# POWER.net
KiCad netlist of a schematic drawn in Altium Designer
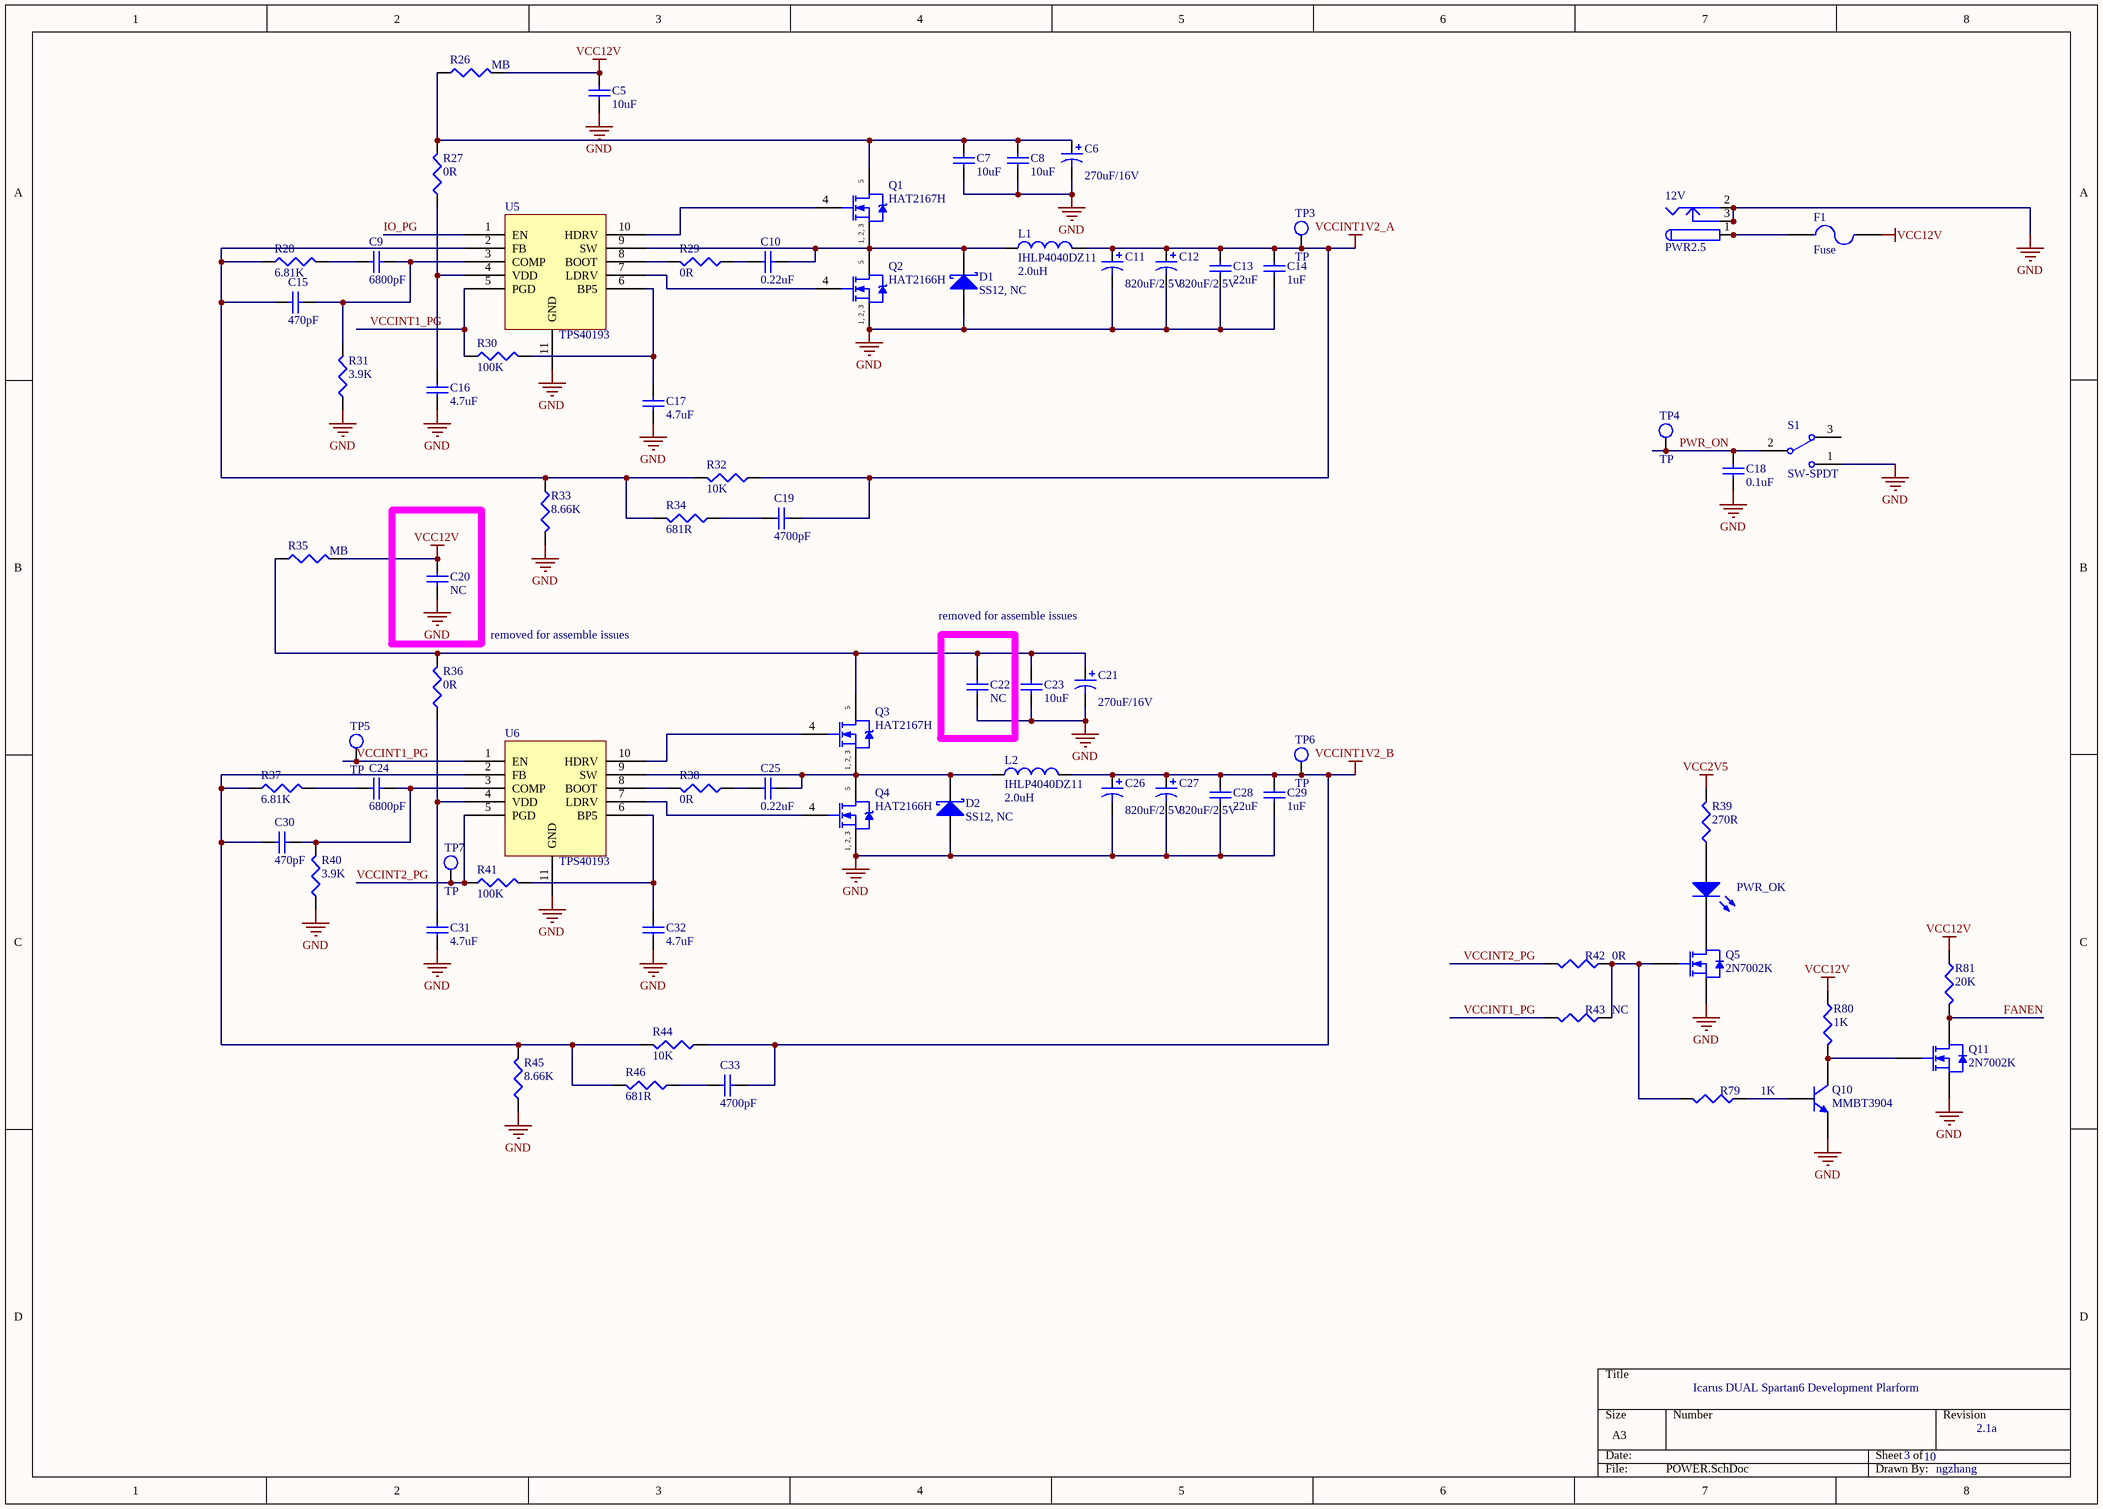
[diagram p0: POWER.SchDoc]

(export (version "E")
  (design (tool "Eeschema 10.0.6"))
  (components
    (comp (ref "12V")
      (value "PWR2.5")
      (footprint "KLD-0202")
      (description "Low Voltage Power Supply Connector")
      (fields (field (name "PUBLISHER") "Altium Limited"))
      (libsource (lib "Miscellaneous Connectors") (part "PWR2.5"))
    )
    (comp (ref "C5")
      (value "10uF")
      (footprint "C1206")
      (description "Capacitor (Semiconductor SIM Model)")
      (fields (field (name "PUBLISHER") "Altium Limited"))
      (libsource (lib "Miscellaneous Devices") (part "Cap Semi"))
    )
    (comp (ref "C6")
      (value "270uF/16V")
      (footprint "CAP8X8")
      (description "Polarized Capacitor (Radial)")
      (fields (field (name "PUBLISHER") "Altium Limited"))
      (libsource (lib "Miscellaneous Devices") (part "Cap Pol1"))
    )
    (comp (ref "C7")
      (value "10uF")
      (footprint "C1206")
      (description "Capacitor (Semiconductor SIM Model)")
      (fields (field (name "PUBLISHER") "Altium Limited"))
      (libsource (lib "Miscellaneous Devices") (part "Cap Semi"))
    )
    (comp (ref "C8")
      (value "10uF")
      (footprint "C1206")
      (description "Capacitor (Semiconductor SIM Model)")
      (fields (field (name "PUBLISHER") "Altium Limited"))
      (libsource (lib "Miscellaneous Devices") (part "Cap Semi"))
    )
    (comp (ref "C9")
      (value "6800pF")
      (footprint "1608[0603]")
      (description "Capacitor (Semiconductor SIM Model)")
      (fields (field (name "PUBLISHER") "Altium Limited"))
      (libsource (lib "Miscellaneous Devices") (part "Cap Semi"))
    )
    (comp (ref "C10")
      (value "0.22uF")
      (footprint "1608[0603]")
      (description "Capacitor (Semiconductor SIM Model)")
      (fields (field (name "PUBLISHER") "Altium Limited"))
      (libsource (lib "Miscellaneous Devices") (part "Cap Semi"))
    )
    (comp (ref "C11")
      (value "820uF/2.5V")
      (footprint "CAP8X8")
      (description "Polarized Capacitor (Radial)")
      (fields (field (name "PUBLISHER") "Altium Limited"))
      (libsource (lib "Miscellaneous Devices") (part "Cap Pol1"))
    )
    (comp (ref "C12")
      (value "820uF/2.5V")
      (footprint "CAP8X8")
      (description "Polarized Capacitor (Radial)")
      (fields (field (name "PUBLISHER") "Altium Limited"))
      (libsource (lib "Miscellaneous Devices") (part "Cap Pol1"))
    )
    (comp (ref "C13")
      (value "22uF")
      (footprint "C1206")
      (description "Capacitor (Semiconductor SIM Model)")
      (fields (field (name "PUBLISHER") "Altium Limited"))
      (libsource (lib "Miscellaneous Devices") (part "Cap Semi"))
    )
    (comp (ref "C14")
      (value "1uF")
      (footprint "1608[0603]")
      (description "Capacitor (Semiconductor SIM Model)")
      (fields (field (name "PUBLISHER") "Altium Limited"))
      (libsource (lib "Miscellaneous Devices") (part "Cap Semi"))
    )
    (comp (ref "C15")
      (value "470pF")
      (footprint "1608[0603]")
      (description "Capacitor (Semiconductor SIM Model)")
      (fields (field (name "PUBLISHER") "Altium Limited"))
      (libsource (lib "Miscellaneous Devices") (part "Cap Semi"))
    )
    (comp (ref "C16")
      (value "4.7uF")
      (footprint "C0805")
      (description "Capacitor (Semiconductor SIM Model)")
      (fields (field (name "PUBLISHER") "Altium Limited"))
      (libsource (lib "Miscellaneous Devices") (part "Cap Semi"))
    )
    (comp (ref "C17")
      (value "4.7uF")
      (footprint "C0805")
      (description "Capacitor (Semiconductor SIM Model)")
      (fields (field (name "PUBLISHER") "Altium Limited"))
      (libsource (lib "Miscellaneous Devices") (part "Cap Semi"))
    )
    (comp (ref "C18")
      (value "0.1uF")
      (footprint "1608[0603]")
      (description "Capacitor (Semiconductor SIM Model)")
      (fields (field (name "PUBLISHER") "Altium Limited"))
      (libsource (lib "Miscellaneous Devices") (part "Cap Semi"))
    )
    (comp (ref "C19")
      (value "4700pF")
      (footprint "1608[0603]")
      (description "Capacitor (Semiconductor SIM Model)")
      (fields (field (name "PUBLISHER") "Altium Limited"))
      (libsource (lib "Miscellaneous Devices") (part "Cap Semi"))
    )
    (comp (ref "C20")
      (value "NC")
      (footprint "C1206")
      (description "Capacitor (Semiconductor SIM Model)")
      (fields (field (name "PUBLISHER") "Altium Limited"))
      (libsource (lib "Miscellaneous Devices") (part "Cap Semi"))
    )
    (comp (ref "C21")
      (value "270uF/16V")
      (footprint "CAP8X8")
      (description "Polarized Capacitor (Radial)")
      (fields (field (name "PUBLISHER") "Altium Limited"))
      (libsource (lib "Miscellaneous Devices") (part "Cap Pol1"))
    )
    (comp (ref "C22")
      (value "NC")
      (footprint "C1206")
      (description "Capacitor (Semiconductor SIM Model)")
      (fields (field (name "PUBLISHER") "Altium Limited"))
      (libsource (lib "Miscellaneous Devices") (part "Cap Semi"))
    )
    (comp (ref "C23")
      (value "10uF")
      (footprint "C1206")
      (description "Capacitor (Semiconductor SIM Model)")
      (fields (field (name "PUBLISHER") "Altium Limited"))
      (libsource (lib "Miscellaneous Devices") (part "Cap Semi"))
    )
    (comp (ref "C24")
      (value "6800pF")
      (footprint "1608[0603]")
      (description "Capacitor (Semiconductor SIM Model)")
      (fields (field (name "PUBLISHER") "Altium Limited"))
      (libsource (lib "Miscellaneous Devices") (part "Cap Semi"))
    )
    (comp (ref "C25")
      (value "0.22uF")
      (footprint "1608[0603]")
      (description "Capacitor (Semiconductor SIM Model)")
      (fields (field (name "PUBLISHER") "Altium Limited"))
      (libsource (lib "Miscellaneous Devices") (part "Cap Semi"))
    )
    (comp (ref "C26")
      (value "820uF/2.5V")
      (footprint "CAP8X8")
      (description "Polarized Capacitor (Radial)")
      (fields (field (name "PUBLISHER") "Altium Limited"))
      (libsource (lib "Miscellaneous Devices") (part "Cap Pol1"))
    )
    (comp (ref "C27")
      (value "820uF/2.5V")
      (footprint "CAP8X8")
      (description "Polarized Capacitor (Radial)")
      (fields (field (name "PUBLISHER") "Altium Limited"))
      (libsource (lib "Miscellaneous Devices") (part "Cap Pol1"))
    )
    (comp (ref "C28")
      (value "22uF")
      (footprint "C1206")
      (description "Capacitor (Semiconductor SIM Model)")
      (fields (field (name "PUBLISHER") "Altium Limited"))
      (libsource (lib "Miscellaneous Devices") (part "Cap Semi"))
    )
    (comp (ref "C29")
      (value "1uF")
      (footprint "1608[0603]")
      (description "Capacitor (Semiconductor SIM Model)")
      (fields (field (name "PUBLISHER") "Altium Limited"))
      (libsource (lib "Miscellaneous Devices") (part "Cap Semi"))
    )
    (comp (ref "C30")
      (value "470pF")
      (footprint "1608[0603]")
      (description "Capacitor (Semiconductor SIM Model)")
      (fields (field (name "PUBLISHER") "Altium Limited"))
      (libsource (lib "Miscellaneous Devices") (part "Cap Semi"))
    )
    (comp (ref "C31")
      (value "4.7uF")
      (footprint "C0805")
      (description "Capacitor (Semiconductor SIM Model)")
      (fields (field (name "PUBLISHER") "Altium Limited"))
      (libsource (lib "Miscellaneous Devices") (part "Cap Semi"))
    )
    (comp (ref "C32")
      (value "4.7uF")
      (footprint "C0805")
      (description "Capacitor (Semiconductor SIM Model)")
      (fields (field (name "PUBLISHER") "Altium Limited"))
      (libsource (lib "Miscellaneous Devices") (part "Cap Semi"))
    )
    (comp (ref "C33")
      (value "4700pF")
      (footprint "1608[0603]")
      (description "Capacitor (Semiconductor SIM Model)")
      (fields (field (name "PUBLISHER") "Altium Limited"))
      (libsource (lib "Miscellaneous Devices") (part "Cap Semi"))
    )
    (comp (ref "D1")
      (value "SS12, NC")
      (footprint "SMA")
      (description "Schottky Rectifier")
      (fields (field (name "PUBLISHER") "Altium Limited"))
      (libsource (lib "IR Rectifier - Schottky") (part "10MQ060N"))
    )
    (comp (ref "D2")
      (value "SS12, NC")
      (footprint "SMA")
      (description "Schottky Rectifier")
      (fields (field (name "PUBLISHER") "Altium Limited"))
      (libsource (lib "IR Rectifier - Schottky") (part "10MQ060N"))
    )
    (comp (ref "F1")
      (value "Fuse")
      (footprint "12Z-2010")
      (fields (field (name "PUBLISHER") "Altium Limited"))
      (libsource (lib "Miscellaneous Devices") (part "Fuse 2"))
    )
    (comp (ref "L1")
      (value "IHLP4040DZ11")
      (footprint "IHLP4040")
      (description "Inductor")
      (fields (field (name "ALTIUM_VALUE") "2.0uH") (field (name "PUBLISHER") "Altium Limited"))
      (libsource (lib "Miscellaneous Devices") (part "Inductor"))
    )
    (comp (ref "L2")
      (value "IHLP4040DZ11")
      (footprint "IHLP4040")
      (description "Inductor")
      (fields (field (name "ALTIUM_VALUE") "2.0uH") (field (name "PUBLISHER") "Altium Limited"))
      (libsource (lib "Miscellaneous Devices") (part "Inductor"))
    )
    (comp (ref "PWR_OK")
      (value "LED3")
      (footprint "CD1608-0603")
      (description "Typical BLUE SiC LED")
      (fields (field (name "PUBLISHER") "Altium Limited"))
      (libsource (lib "Miscellaneous Devices") (part "LED3"))
    )
    (comp (ref "Q1") (value "HAT2167H") (footprint "LFPAK") (libsource (lib "S6") (part "HAT216X")))
    (comp (ref "Q2") (value "HAT2166H") (footprint "LFPAK") (libsource (lib "S6") (part "HAT216X")))
    (comp (ref "Q3") (value "HAT2167H") (footprint "LFPAK") (libsource (lib "S6") (part "HAT216X")))
    (comp (ref "Q4") (value "HAT2166H") (footprint "LFPAK") (libsource (lib "S6") (part "HAT216X")))
    (comp (ref "Q5")
      (value "2N7002K")
      (footprint "SOT23_N")
      (description "N-channel Enhancement Mode Field-effect Transistor")
      (fields (field (name "PUBLISHER") "Altium Limited"))
      (libsource (lib "Philips Discrete MOSFET - Low Power") (part "2N7002"))
    )
    (comp (ref "Q10")
      (value "MMBT3904")
      (footprint "SOT23_N")
      (description "NPN Switching Transistor")
      (fields (field (name "PUBLISHER") "Altium Limited"))
      (libsource (lib "Philips Discrete BJT - Low Power") (part "MMBT3904"))
    )
    (comp (ref "Q11")
      (value "2N7002K")
      (footprint "SOT23_N")
      (description "N-channel Enhancement Mode Field-effect Transistor")
      (fields (field (name "PUBLISHER") "Altium Limited"))
      (libsource (lib "Philips Discrete MOSFET - Low Power") (part "2N7002"))
    )
    (comp (ref "R26")
      (value "MB")
      (footprint "C1206")
      (description "Resistor")
      (fields (field (name "PUBLISHER") "Altium Limited"))
      (libsource (lib "Miscellaneous Devices") (part "Res3"))
    )
    (comp (ref "R27")
      (value "0R")
      (footprint "J1-0603")
      (description "Resistor")
      (fields (field (name "PUBLISHER") "Altium Limited"))
      (libsource (lib "Miscellaneous Devices") (part "Res3"))
    )
    (comp (ref "R28")
      (value "6.81K")
      (footprint "J1-0603")
      (description "Resistor")
      (fields (field (name "PUBLISHER") "Altium Limited"))
      (libsource (lib "Miscellaneous Devices") (part "Res3"))
    )
    (comp (ref "R29")
      (value "0R")
      (footprint "J1-0603")
      (description "Resistor")
      (fields (field (name "PUBLISHER") "Altium Limited"))
      (libsource (lib "Miscellaneous Devices") (part "Res3"))
    )
    (comp (ref "R30")
      (value "100K")
      (footprint "J1-0603")
      (description "Resistor")
      (fields (field (name "PUBLISHER") "Altium Limited"))
      (libsource (lib "Miscellaneous Devices") (part "Res3"))
    )
    (comp (ref "R31")
      (value "3.9K")
      (footprint "J1-0603")
      (description "Resistor")
      (fields (field (name "PUBLISHER") "Altium Limited"))
      (libsource (lib "Miscellaneous Devices") (part "Res3"))
    )
    (comp (ref "R32")
      (value "10K")
      (footprint "J1-0603")
      (description "Resistor")
      (fields (field (name "PUBLISHER") "Altium Limited"))
      (libsource (lib "Miscellaneous Devices") (part "Res3"))
    )
    (comp (ref "R33")
      (value "8.66K")
      (footprint "J1-0603")
      (description "Resistor")
      (fields (field (name "PUBLISHER") "Altium Limited"))
      (libsource (lib "Miscellaneous Devices") (part "Res3"))
    )
    (comp (ref "R34")
      (value "681R")
      (footprint "J1-0603")
      (description "Resistor")
      (fields (field (name "PUBLISHER") "Altium Limited"))
      (libsource (lib "Miscellaneous Devices") (part "Res3"))
    )
    (comp (ref "R35")
      (value "MB")
      (footprint "C1206")
      (description "Resistor")
      (fields (field (name "PUBLISHER") "Altium Limited"))
      (libsource (lib "Miscellaneous Devices") (part "Res3"))
    )
    (comp (ref "R36")
      (value "0R")
      (footprint "J1-0603")
      (description "Resistor")
      (fields (field (name "PUBLISHER") "Altium Limited"))
      (libsource (lib "Miscellaneous Devices") (part "Res3"))
    )
    (comp (ref "R37")
      (value "6.81K")
      (footprint "J1-0603")
      (description "Resistor")
      (fields (field (name "PUBLISHER") "Altium Limited"))
      (libsource (lib "Miscellaneous Devices") (part "Res3"))
    )
    (comp (ref "R38")
      (value "0R")
      (footprint "J1-0603")
      (description "Resistor")
      (fields (field (name "PUBLISHER") "Altium Limited"))
      (libsource (lib "Miscellaneous Devices") (part "Res3"))
    )
    (comp (ref "R39")
      (value "270R")
      (footprint "J1-0603")
      (description "Resistor")
      (fields (field (name "PUBLISHER") "Altium Limited"))
      (libsource (lib "Miscellaneous Devices") (part "Res3"))
    )
    (comp (ref "R40")
      (value "3.9K")
      (footprint "J1-0603")
      (description "Resistor")
      (fields (field (name "PUBLISHER") "Altium Limited"))
      (libsource (lib "Miscellaneous Devices") (part "Res3"))
    )
    (comp (ref "R41")
      (value "100K")
      (footprint "J1-0603")
      (description "Resistor")
      (fields (field (name "PUBLISHER") "Altium Limited"))
      (libsource (lib "Miscellaneous Devices") (part "Res3"))
    )
    (comp (ref "R42")
      (value "0R")
      (footprint "J1-0603")
      (description "Resistor")
      (fields (field (name "PUBLISHER") "Altium Limited"))
      (libsource (lib "Miscellaneous Devices") (part "Res3"))
    )
    (comp (ref "R43")
      (value "NC")
      (footprint "J1-0603")
      (description "Resistor")
      (fields (field (name "PUBLISHER") "Altium Limited"))
      (libsource (lib "Miscellaneous Devices") (part "Res3"))
    )
    (comp (ref "R44")
      (value "10K")
      (footprint "J1-0603")
      (description "Resistor")
      (fields (field (name "PUBLISHER") "Altium Limited"))
      (libsource (lib "Miscellaneous Devices") (part "Res3"))
    )
    (comp (ref "R45")
      (value "8.66K")
      (footprint "J1-0603")
      (description "Resistor")
      (fields (field (name "PUBLISHER") "Altium Limited"))
      (libsource (lib "Miscellaneous Devices") (part "Res3"))
    )
    (comp (ref "R46")
      (value "681R")
      (footprint "J1-0603")
      (description "Resistor")
      (fields (field (name "PUBLISHER") "Altium Limited"))
      (libsource (lib "Miscellaneous Devices") (part "Res3"))
    )
    (comp (ref "R79")
      (value "1K")
      (footprint "J1-0603")
      (description "Resistor")
      (fields (field (name "PUBLISHER") "Altium Limited"))
      (libsource (lib "Miscellaneous Devices") (part "Res3"))
    )
    (comp (ref "R80")
      (value "1K")
      (footprint "J1-0603")
      (description "Resistor")
      (fields (field (name "PUBLISHER") "Altium Limited"))
      (libsource (lib "Miscellaneous Devices") (part "Res3"))
    )
    (comp (ref "R81")
      (value "20K")
      (footprint "J1-0603")
      (description "Resistor")
      (fields (field (name "PUBLISHER") "Altium Limited"))
      (libsource (lib "Miscellaneous Devices") (part "Res3"))
    )
    (comp (ref "S1")
      (value "SW-SPDT")
      (footprint "SW_3")
      (description "SPDT Subminiature Toggle Switch, Right Angle Mounting, Vertical Actuation")
      (fields (field (name "PUBLISHER") "Altium Limited"))
      (libsource (lib "Miscellaneous Devices") (part "SW-SPDT"))
    )
    (comp (ref "TP3") (value "TP") (footprint "TP") (libsource (lib "S6") (part "TP")))
    (comp (ref "TP4") (value "TP") (footprint "TP") (libsource (lib "S6") (part "TP")))
    (comp (ref "TP5") (value "TP") (footprint "TP") (libsource (lib "S6") (part "TP")))
    (comp (ref "TP6") (value "TP") (footprint "TP") (libsource (lib "S6") (part "TP")))
    (comp (ref "TP7") (value "TP") (footprint "TP") (libsource (lib "S6") (part "TP")))
    (comp (ref "U5") (value "TPS40193") (footprint "SON10") (libsource (lib "S6") (part "TPS40193")))
    (comp (ref "U6") (value "TPS40193") (footprint "SON10") (libsource (lib "S6") (part "TPS40193")))
  )
  (nets
    (net (code "1") (name "/FANEN") (class "Default")
      (node (ref "Q11") (pin "3") (pinfunction "D_3") (pintype "passive"))
      (node (ref "R81") (pin "2") (pinfunction "2_2") (pintype "passive"))
    )
    (net (code "2") (name "/IO_PG") (class "Default")
      (node (ref "U5") (pin "1") (pinfunction "EN_1") (pintype "passive"))
    )
    (net (code "3") (name "/PWR_ON") (class "Default")
      (node (ref "C18") (pin "2") (pinfunction "2_2") (pintype "passive"))
      (node (ref "S1") (pin "2") (pinfunction "2_2") (pintype "passive"))
      (node (ref "TP4") (pin "1") (pinfunction "TP_1") (pintype "passive"))
    )
    (net (code "4") (name "/VCCINT1_PG") (class "Default")
      (node (ref "R30") (pin "1") (pinfunction "1_1") (pintype "passive"))
      (node (ref "R43") (pin "2") (pinfunction "2_2") (pintype "passive"))
      (node (ref "TP5") (pin "1") (pinfunction "TP_1") (pintype "passive"))
      (node (ref "U5") (pin "5") (pinfunction "PGD_5") (pintype "passive"))
      (node (ref "U6") (pin "1") (pinfunction "EN_1") (pintype "passive"))
    )
    (net (code "5") (name "/VCCINT2_PG") (class "Default")
      (node (ref "R41") (pin "1") (pinfunction "1_1") (pintype "passive"))
      (node (ref "R42") (pin "2") (pinfunction "2_2") (pintype "passive"))
      (node (ref "TP7") (pin "1") (pinfunction "TP_1") (pintype "passive"))
      (node (ref "U6") (pin "5") (pinfunction "PGD_5") (pintype "passive"))
    )
    (net (code "6") (name "GND") (class "Default")
      (node (ref "12V") (pin "2") (pinfunction "2_2") (pintype "power_in"))
      (node (ref "12V") (pin "2A") (pinfunction "2A_2A") (pintype "power_in"))
      (node (ref "12V") (pin "2B") (pinfunction "2B_2B") (pintype "power_in"))
      (node (ref "12V") (pin "3") (pinfunction "3_3") (pintype "power_in"))
      (node (ref "12V") (pin "3A") (pinfunction "3A_3A") (pintype "power_in"))
      (node (ref "12V") (pin "3B") (pinfunction "3B_3B") (pintype "power_in"))
      (node (ref "C11") (pin "2") (pinfunction "2_2") (pintype "passive"))
      (node (ref "C12") (pin "2") (pinfunction "2_2") (pintype "passive"))
      (node (ref "C13") (pin "1") (pinfunction "1_1") (pintype "passive"))
      (node (ref "C14") (pin "1") (pinfunction "1_1") (pintype "passive"))
      (node (ref "C16") (pin "2") (pinfunction "2_2") (pintype "passive"))
      (node (ref "C17") (pin "1") (pinfunction "1_1") (pintype "passive"))
      (node (ref "C18") (pin "1") (pinfunction "1_1") (pintype "passive"))
      (node (ref "C20") (pin "1") (pinfunction "1_1") (pintype "passive"))
      (node (ref "C21") (pin "2") (pinfunction "2_2") (pintype "passive"))
      (node (ref "C22") (pin "1") (pinfunction "1_1") (pintype "passive"))
      (node (ref "C23") (pin "1") (pinfunction "1_1") (pintype "passive"))
      (node (ref "C26") (pin "2") (pinfunction "2_2") (pintype "passive"))
      (node (ref "C27") (pin "2") (pinfunction "2_2") (pintype "passive"))
      (node (ref "C28") (pin "1") (pinfunction "1_1") (pintype "passive"))
      (node (ref "C29") (pin "1") (pinfunction "1_1") (pintype "passive"))
      (node (ref "C31") (pin "1") (pinfunction "1_1") (pintype "passive"))
      (node (ref "C32") (pin "2") (pinfunction "2_2") (pintype "passive"))
      (node (ref "C5") (pin "1") (pinfunction "1_1") (pintype "passive"))
      (node (ref "C6") (pin "2") (pinfunction "2_2") (pintype "passive"))
      (node (ref "C7") (pin "1") (pinfunction "1_1") (pintype "passive"))
      (node (ref "C8") (pin "1") (pinfunction "1_1") (pintype "passive"))
      (node (ref "D1") (pin "1") (pinfunction "A_1") (pintype "passive"))
      (node (ref "D2") (pin "1") (pinfunction "A_1") (pintype "passive"))
      (node (ref "Q10") (pin "2") (pinfunction "E_2") (pintype "passive"))
      (node (ref "Q11") (pin "2") (pinfunction "S_2") (pintype "passive"))
      (node (ref "Q2") (pin "1") (pinfunction "S_1") (pintype "passive"))
      (node (ref "Q2") (pin "2") (pinfunction "S_2") (pintype "passive"))
      (node (ref "Q2") (pin "3") (pinfunction "S_3") (pintype "passive"))
      (node (ref "Q4") (pin "1") (pinfunction "S_1") (pintype "passive"))
      (node (ref "Q4") (pin "2") (pinfunction "S_2") (pintype "passive"))
      (node (ref "Q4") (pin "3") (pinfunction "S_3") (pintype "passive"))
      (node (ref "Q5") (pin "2") (pinfunction "S_2") (pintype "passive"))
      (node (ref "R31") (pin "1") (pinfunction "1_1") (pintype "passive"))
      (node (ref "R33") (pin "2") (pinfunction "2_2") (pintype "passive"))
      (node (ref "R40") (pin "1") (pinfunction "1_1") (pintype "passive"))
      (node (ref "R45") (pin "1") (pinfunction "1_1") (pintype "passive"))
      (node (ref "S1") (pin "1") (pinfunction "1_1") (pintype "passive"))
      (node (ref "U5") (pin "11") (pinfunction "GND_11") (pintype "passive"))
      (node (ref "U6") (pin "11") (pinfunction "GND_11") (pintype "passive"))
    )
    (net (code "7") (name "Net-(12V-Pad1)") (class "Default")
      (node (ref "12V") (pin "1") (pinfunction "1_1") (pintype "power_in"))
      (node (ref "12V") (pin "1A") (pinfunction "1A_1A") (pintype "power_in"))
      (node (ref "12V") (pin "1B") (pinfunction "1B_1B") (pintype "power_in"))
      (node (ref "F1") (pin "1") (pinfunction "1_1") (pintype "passive"))
    )
    (net (code "8") (name "Net-(C9-Pad2)") (class "Default")
      (node (ref "C9") (pin "2") (pinfunction "2_2") (pintype "passive"))
      (node (ref "R28") (pin "2") (pinfunction "2_2") (pintype "passive"))
    )
    (net (code "9") (name "Net-(C10-Pad2)") (class "Default")
      (node (ref "C10") (pin "2") (pinfunction "2_2") (pintype "passive"))
      (node (ref "R29") (pin "1") (pinfunction "1_1") (pintype "passive"))
    )
    (net (code "10") (name "Net-(C19-Pad1)") (class "Default")
      (node (ref "C19") (pin "1") (pinfunction "1_1") (pintype "passive"))
      (node (ref "R34") (pin "1") (pinfunction "1_1") (pintype "passive"))
    )
    (net (code "11") (name "Net-(C24-Pad2)") (class "Default")
      (node (ref "C24") (pin "2") (pinfunction "2_2") (pintype "passive"))
      (node (ref "R37") (pin "2") (pinfunction "2_2") (pintype "passive"))
    )
    (net (code "12") (name "Net-(C25-Pad2)") (class "Default")
      (node (ref "C25") (pin "2") (pinfunction "2_2") (pintype "passive"))
      (node (ref "R38") (pin "1") (pinfunction "1_1") (pintype "passive"))
    )
    (net (code "13") (name "Net-(C33-Pad1)") (class "Default")
      (node (ref "C33") (pin "1") (pinfunction "1_1") (pintype "passive"))
      (node (ref "R46") (pin "1") (pinfunction "1_1") (pintype "passive"))
    )
    (net (code "14") (name "Net-(D1-K)") (class "Default")
      (node (ref "C10") (pin "1") (pinfunction "1_1") (pintype "passive"))
      (node (ref "D1") (pin "2") (pinfunction "K_2") (pintype "passive"))
      (node (ref "L1") (pin "1") (pinfunction "1_1") (pintype "passive"))
      (node (ref "Q1") (pin "1") (pinfunction "S_1") (pintype "passive"))
      (node (ref "Q1") (pin "2") (pinfunction "S_2") (pintype "passive"))
      (node (ref "Q1") (pin "3") (pinfunction "S_3") (pintype "passive"))
      (node (ref "Q2") (pin "5") (pinfunction "D_5") (pintype "passive"))
      (node (ref "U5") (pin "9") (pinfunction "SW_9") (pintype "passive"))
    )
    (net (code "15") (name "Net-(D2-K)") (class "Default")
      (node (ref "C25") (pin "1") (pinfunction "1_1") (pintype "passive"))
      (node (ref "D2") (pin "2") (pinfunction "K_2") (pintype "passive"))
      (node (ref "L2") (pin "1") (pinfunction "1_1") (pintype "passive"))
      (node (ref "Q3") (pin "1") (pinfunction "S_1") (pintype "passive"))
      (node (ref "Q3") (pin "2") (pinfunction "S_2") (pintype "passive"))
      (node (ref "Q3") (pin "3") (pinfunction "S_3") (pintype "passive"))
      (node (ref "Q4") (pin "5") (pinfunction "D_5") (pintype "passive"))
      (node (ref "U6") (pin "9") (pinfunction "SW_9") (pintype "passive"))
    )
    (net (code "16") (name "Net-(PWR_OK-A)") (class "Default")
      (node (ref "PWR_OK") (pin "1") (pinfunction "A_1") (pintype "passive"))
      (node (ref "R39") (pin "1") (pinfunction "1_1") (pintype "passive"))
    )
    (net (code "17") (name "Net-(PWR_OK-K)") (class "Default")
      (node (ref "PWR_OK") (pin "2") (pinfunction "K_2") (pintype "passive"))
      (node (ref "Q5") (pin "3") (pinfunction "D_3") (pintype "passive"))
    )
    (net (code "18") (name "Net-(Q1-D)") (class "Default")
      (node (ref "C6") (pin "1") (pinfunction "1_1") (pintype "passive"))
      (node (ref "C7") (pin "2") (pinfunction "2_2") (pintype "passive"))
      (node (ref "C8") (pin "2") (pinfunction "2_2") (pintype "passive"))
      (node (ref "Q1") (pin "5") (pinfunction "D_5") (pintype "passive"))
      (node (ref "R26") (pin "1") (pinfunction "1_1") (pintype "passive"))
      (node (ref "R27") (pin "2") (pinfunction "2_2") (pintype "passive"))
    )
    (net (code "19") (name "Net-(Q1-G)") (class "Default")
      (node (ref "Q1") (pin "4") (pinfunction "G_4") (pintype "passive"))
      (node (ref "U5") (pin "10") (pinfunction "HDRV_10") (pintype "passive"))
    )
    (net (code "20") (name "Net-(Q2-G)") (class "Default")
      (node (ref "Q2") (pin "4") (pinfunction "G_4") (pintype "passive"))
      (node (ref "U5") (pin "7") (pinfunction "LDRV_7") (pintype "passive"))
    )
    (net (code "21") (name "Net-(Q3-D)") (class "Default")
      (node (ref "C21") (pin "1") (pinfunction "1_1") (pintype "passive"))
      (node (ref "C22") (pin "2") (pinfunction "2_2") (pintype "passive"))
      (node (ref "C23") (pin "2") (pinfunction "2_2") (pintype "passive"))
      (node (ref "Q3") (pin "5") (pinfunction "D_5") (pintype "passive"))
      (node (ref "R35") (pin "1") (pinfunction "1_1") (pintype "passive"))
      (node (ref "R36") (pin "2") (pinfunction "2_2") (pintype "passive"))
    )
    (net (code "22") (name "Net-(Q3-G)") (class "Default")
      (node (ref "Q3") (pin "4") (pinfunction "G_4") (pintype "passive"))
      (node (ref "U6") (pin "10") (pinfunction "HDRV_10") (pintype "passive"))
    )
    (net (code "23") (name "Net-(Q4-G)") (class "Default")
      (node (ref "Q4") (pin "4") (pinfunction "G_4") (pintype "passive"))
      (node (ref "U6") (pin "7") (pinfunction "LDRV_7") (pintype "passive"))
    )
    (net (code "24") (name "Net-(Q5-G)") (class "Default")
      (node (ref "Q5") (pin "1") (pinfunction "G_1") (pintype "passive"))
      (node (ref "R42") (pin "1") (pinfunction "1_1") (pintype "passive"))
      (node (ref "R43") (pin "1") (pinfunction "1_1") (pintype "passive"))
      (node (ref "R79") (pin "2") (pinfunction "2_2") (pintype "passive"))
    )
    (net (code "25") (name "Net-(Q10-B)") (class "Default")
      (node (ref "Q10") (pin "1") (pinfunction "B_1") (pintype "passive"))
      (node (ref "R79") (pin "1") (pinfunction "1_1") (pintype "passive"))
    )
    (net (code "26") (name "Net-(Q10-C)") (class "Default")
      (node (ref "Q10") (pin "3") (pinfunction "C_3") (pintype "passive"))
      (node (ref "Q11") (pin "1") (pinfunction "G_1") (pintype "passive"))
      (node (ref "R80") (pin "2") (pinfunction "2_2") (pintype "passive"))
    )
    (net (code "27") (name "Net-(U5-BOOT)") (class "Default")
      (node (ref "R29") (pin "2") (pinfunction "2_2") (pintype "passive"))
      (node (ref "U5") (pin "8") (pinfunction "BOOT_8") (pintype "passive"))
    )
    (net (code "28") (name "Net-(U5-BP5)") (class "Default")
      (node (ref "C17") (pin "2") (pinfunction "2_2") (pintype "passive"))
      (node (ref "R30") (pin "2") (pinfunction "2_2") (pintype "passive"))
      (node (ref "U5") (pin "6") (pinfunction "BP5_6") (pintype "passive"))
    )
    (net (code "29") (name "Net-(U5-COMP)") (class "Default")
      (node (ref "C15") (pin "1") (pinfunction "1_1") (pintype "passive"))
      (node (ref "C9") (pin "1") (pinfunction "1_1") (pintype "passive"))
      (node (ref "R31") (pin "2") (pinfunction "2_2") (pintype "passive"))
      (node (ref "U5") (pin "3") (pinfunction "COMP_3") (pintype "passive"))
    )
    (net (code "30") (name "Net-(U5-FB)") (class "Default")
      (node (ref "C15") (pin "2") (pinfunction "2_2") (pintype "passive"))
      (node (ref "R28") (pin "1") (pinfunction "1_1") (pintype "passive"))
      (node (ref "R32") (pin "2") (pinfunction "2_2") (pintype "passive"))
      (node (ref "R33") (pin "1") (pinfunction "1_1") (pintype "passive"))
      (node (ref "R34") (pin "2") (pinfunction "2_2") (pintype "passive"))
      (node (ref "U5") (pin "2") (pinfunction "FB_2") (pintype "passive"))
    )
    (net (code "31") (name "Net-(U5-VDD)") (class "Default")
      (node (ref "C16") (pin "1") (pinfunction "1_1") (pintype "passive"))
      (node (ref "R27") (pin "1") (pinfunction "1_1") (pintype "passive"))
      (node (ref "U5") (pin "4") (pinfunction "VDD_4") (pintype "passive"))
    )
    (net (code "32") (name "Net-(U6-BOOT)") (class "Default")
      (node (ref "R38") (pin "2") (pinfunction "2_2") (pintype "passive"))
      (node (ref "U6") (pin "8") (pinfunction "BOOT_8") (pintype "passive"))
    )
    (net (code "33") (name "Net-(U6-BP5)") (class "Default")
      (node (ref "C32") (pin "1") (pinfunction "1_1") (pintype "passive"))
      (node (ref "R41") (pin "2") (pinfunction "2_2") (pintype "passive"))
      (node (ref "U6") (pin "6") (pinfunction "BP5_6") (pintype "passive"))
    )
    (net (code "34") (name "Net-(U6-COMP)") (class "Default")
      (node (ref "C24") (pin "1") (pinfunction "1_1") (pintype "passive"))
      (node (ref "C30") (pin "1") (pinfunction "1_1") (pintype "passive"))
      (node (ref "R40") (pin "2") (pinfunction "2_2") (pintype "passive"))
      (node (ref "U6") (pin "3") (pinfunction "COMP_3") (pintype "passive"))
    )
    (net (code "35") (name "Net-(U6-FB)") (class "Default")
      (node (ref "C30") (pin "2") (pinfunction "2_2") (pintype "passive"))
      (node (ref "R37") (pin "1") (pinfunction "1_1") (pintype "passive"))
      (node (ref "R44") (pin "2") (pinfunction "2_2") (pintype "passive"))
      (node (ref "R45") (pin "2") (pinfunction "2_2") (pintype "passive"))
      (node (ref "R46") (pin "2") (pinfunction "2_2") (pintype "passive"))
      (node (ref "U6") (pin "2") (pinfunction "FB_2") (pintype "passive"))
    )
    (net (code "36") (name "Net-(U6-VDD)") (class "Default")
      (node (ref "C31") (pin "2") (pinfunction "2_2") (pintype "passive"))
      (node (ref "R36") (pin "1") (pinfunction "1_1") (pintype "passive"))
      (node (ref "U6") (pin "4") (pinfunction "VDD_4") (pintype "passive"))
    )
    (net (code "37") (name "VCC2V5") (class "Default")
      (node (ref "R39") (pin "2") (pinfunction "2_2") (pintype "passive"))
    )
    (net (code "38") (name "VCC12V") (class "Default")
      (node (ref "C20") (pin "2") (pinfunction "2_2") (pintype "passive"))
      (node (ref "C5") (pin "2") (pinfunction "2_2") (pintype "passive"))
      (node (ref "F1") (pin "2") (pinfunction "2_2") (pintype "passive"))
      (node (ref "R26") (pin "2") (pinfunction "2_2") (pintype "passive"))
      (node (ref "R35") (pin "2") (pinfunction "2_2") (pintype "passive"))
      (node (ref "R80") (pin "1") (pinfunction "1_1") (pintype "passive"))
      (node (ref "R81") (pin "1") (pinfunction "1_1") (pintype "passive"))
    )
    (net (code "39") (name "VCCINT1V2_A") (class "Default")
      (node (ref "C11") (pin "1") (pinfunction "1_1") (pintype "passive"))
      (node (ref "C12") (pin "1") (pinfunction "1_1") (pintype "passive"))
      (node (ref "C13") (pin "2") (pinfunction "2_2") (pintype "passive"))
      (node (ref "C14") (pin "2") (pinfunction "2_2") (pintype "passive"))
      (node (ref "C19") (pin "2") (pinfunction "2_2") (pintype "passive"))
      (node (ref "L1") (pin "2") (pinfunction "2_2") (pintype "passive"))
      (node (ref "R32") (pin "1") (pinfunction "1_1") (pintype "passive"))
      (node (ref "TP3") (pin "1") (pinfunction "TP_1") (pintype "passive"))
    )
    (net (code "40") (name "VCCINT1V2_B") (class "Default")
      (node (ref "C26") (pin "1") (pinfunction "1_1") (pintype "passive"))
      (node (ref "C27") (pin "1") (pinfunction "1_1") (pintype "passive"))
      (node (ref "C28") (pin "2") (pinfunction "2_2") (pintype "passive"))
      (node (ref "C29") (pin "2") (pinfunction "2_2") (pintype "passive"))
      (node (ref "C33") (pin "2") (pinfunction "2_2") (pintype "passive"))
      (node (ref "L2") (pin "2") (pinfunction "2_2") (pintype "passive"))
      (node (ref "R44") (pin "1") (pinfunction "1_1") (pintype "passive"))
      (node (ref "TP6") (pin "1") (pinfunction "TP_1") (pintype "passive"))
    )
    (net (code "41") (name "unconnected-(S1-Pad3)") (class "Default")
      (node (ref "S1") (pin "3") (pinfunction "3_3") (pintype "passive"))
    )
  )
)
